# supply_filter.net
KiCad netlist of a schematic drawn in Altium Designer
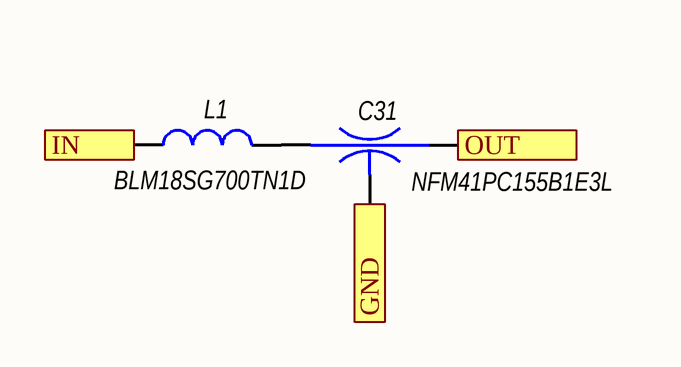
[diagram p0: supply_filter.SchDoc]

(export (version "E")
  (design (tool "Eeschema 10.0.6"))
  (components
    (comp (ref "C31")
      (value "NFM41PC155B1E3L")
      (footprint "FIL_NFM41PC155B1E3L")
      (description "Емкостной фильтр проходной")
      (libsource (lib "SCH_LIB") (part "Capacity_filtr"))
    )
    (comp (ref "L1")
      (value "BLM18SG700TN1D")
      (footprint "RES_0603")
      (description "Дроссель ЭМП")
      (libsource (lib "SCH_LIB") (part "FERRITE_BEAD"))
    )
  )
  (nets
    (net (code "1") (name "/GND") (class "Default") (node (ref "C31") (pin "2") (pintype "passive")))
    (net (code "2") (name "/IN") (class "Default")
      (node (ref "L1") (pin "2") (pinfunction "8_2") (pintype "passive"))
    )
    (net (code "3") (name "/OUT") (class "Default") (node (ref "C31") (pin "3") (pintype "passive")))
    (net (code "4") (name "Net-(L1-7)") (class "Default")
      (node (ref "C31") (pin "1") (pintype "passive"))
      (node (ref "L1") (pin "1") (pinfunction "7_1") (pintype "passive"))
    )
  )
)
